# ParCar.net
KiCad netlist of a schematic drawn in Altium Designer
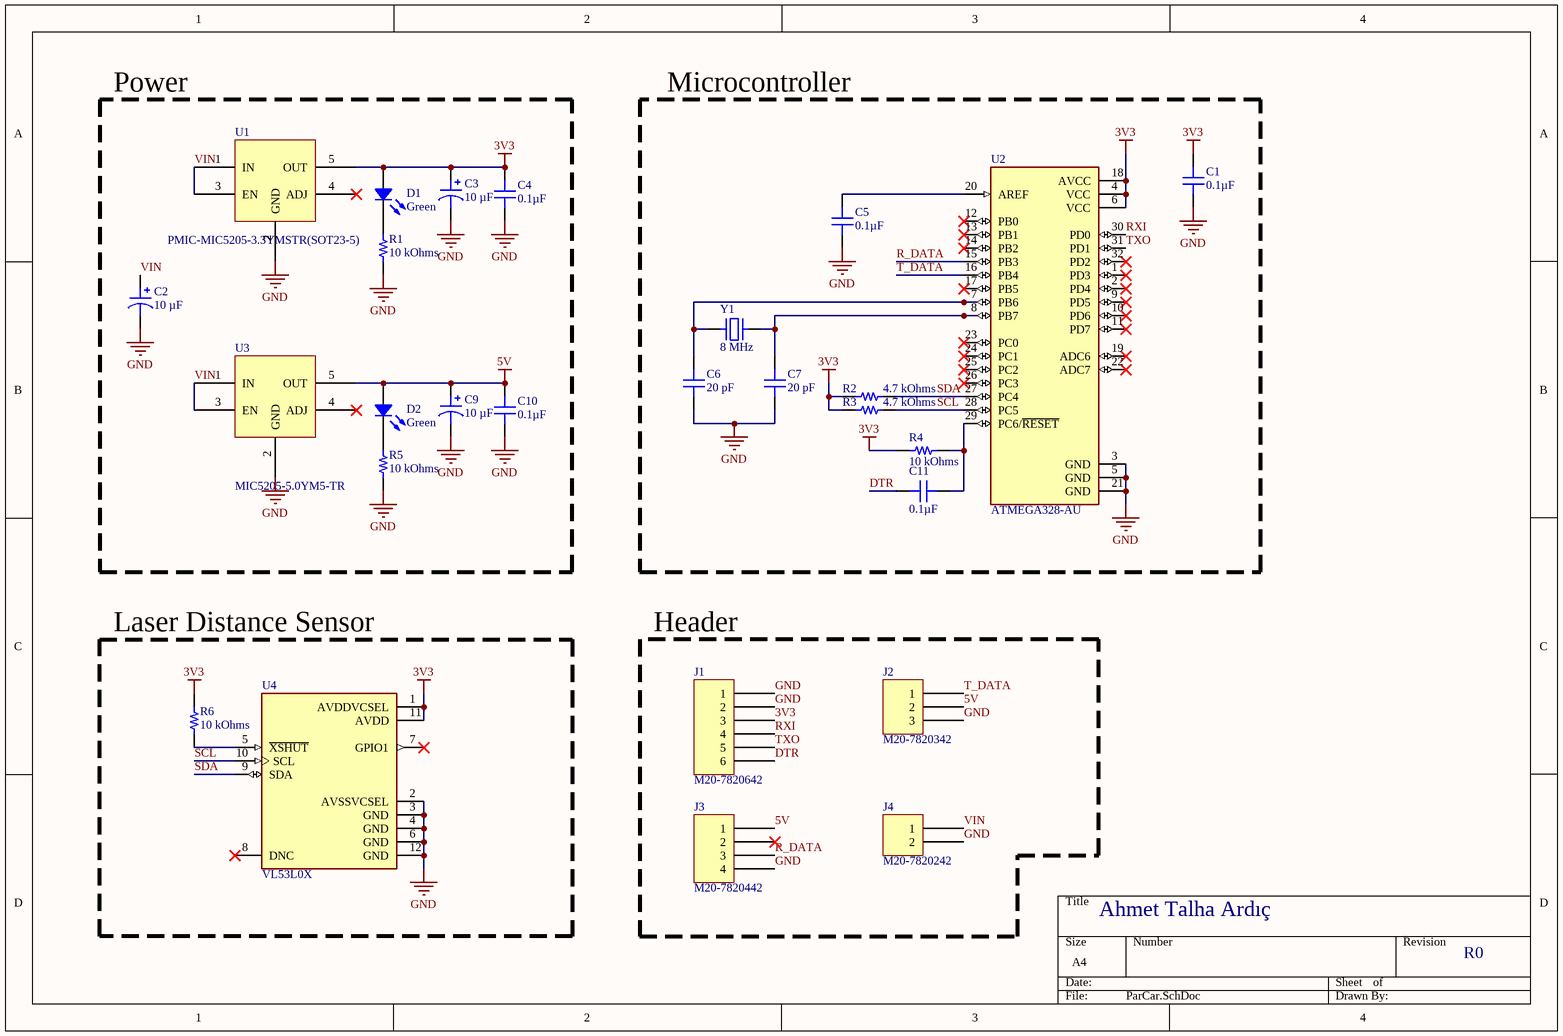
[diagram p0: ParCar.SchDoc]

(export (version "E")
  (design (tool "Eeschema 10.0.6"))
  (components
    (comp (ref "C1")
      (value "0.1µF")
      (footprint "CAP 0603_1608")
      (description "CAP CER 0.1UF 6.3V X7R 0603")
      (fields (field (name "PART NUMBER") "06036C104JAT2A") (field (name "MANUFACTURER") "AVX Corporation"))
      (libsource (lib "Celestial Altium Library - altium_library") (part "Capacitor"))
    )
    (comp (ref "C2")
      (value "10 µF")
      (footprint "CAP ALSMD 4.3MM H5.4MM")
      (description "CAP ALUM 10UF 20% 16V SMD")
      (fields (field (name "PART NUMBER") "UWX1C100MCL1GB") (field (name "MANUFACTURER") "Nichicon"))
      (libsource (lib "Celestial Altium Library - altium_library") (part "Polarised Capacitor"))
    )
    (comp (ref "C3")
      (value "10 µF")
      (footprint "CAP ALSMD 4.3MM H5.4MM")
      (description "CAP ALUM 10UF 20% 16V SMD")
      (fields (field (name "PART NUMBER") "UWX1C100MCL1GB") (field (name "MANUFACTURER") "Nichicon"))
      (libsource (lib "Celestial Altium Library - altium_library") (part "Polarised Capacitor"))
    )
    (comp (ref "C4")
      (value "0.1µF")
      (footprint "CAP 0603_1608")
      (description "CAP CER 0.1UF 6.3V X7R 0603")
      (fields (field (name "PART NUMBER") "06036C104JAT2A") (field (name "MANUFACTURER") "AVX Corporation"))
      (libsource (lib "Celestial Altium Library - altium_library") (part "Capacitor"))
    )
    (comp (ref "C5")
      (value "0.1µF")
      (footprint "CAP 0603_1608")
      (description "CAP CER 0.1UF 6.3V X7R 0603")
      (fields (field (name "PART NUMBER") "06036C104JAT2A") (field (name "MANUFACTURER") "AVX Corporation"))
      (libsource (lib "Celestial Altium Library - altium_library") (part "Capacitor"))
    )
    (comp (ref "C6")
      (value "20 pF")
      (footprint "CAP 0603_1608")
      (description "CAP CER 20PF 10V X8R 0603")
      (fields (field (name "PART NUMBER") "C0603C200G8HAC7867") (field (name "MANUFACTURER") "KEMET"))
      (libsource (lib "Celestial Altium Library - altium_library") (part "Capacitor"))
    )
    (comp (ref "C7")
      (value "20 pF")
      (footprint "CAP 0603_1608")
      (description "CAP CER 20PF 10V X8R 0603")
      (fields (field (name "PART NUMBER") "C0603C200G8HAC7867") (field (name "MANUFACTURER") "KEMET"))
      (libsource (lib "Celestial Altium Library - altium_library") (part "Capacitor"))
    )
    (comp (ref "C9")
      (value "10 µF")
      (footprint "CAP ALSMD 4.3MM H5.4MM")
      (description "CAP ALUM 10UF 20% 16V SMD")
      (fields (field (name "PART NUMBER") "UWX1C100MCL1GB") (field (name "MANUFACTURER") "Nichicon"))
      (libsource (lib "Celestial Altium Library - altium_library") (part "Polarised Capacitor"))
    )
    (comp (ref "C10")
      (value "0.1µF")
      (footprint "CAP 0603_1608")
      (description "CAP CER 0.1UF 6.3V X7R 0603")
      (fields (field (name "PART NUMBER") "06036C104JAT2A") (field (name "MANUFACTURER") "AVX Corporation"))
      (libsource (lib "Celestial Altium Library - altium_library") (part "Capacitor"))
    )
    (comp (ref "C11")
      (value "0.1µF")
      (footprint "CAP 0603_1608")
      (description "CAP CER 0.1UF 6.3V X7R 0603")
      (fields (field (name "PART NUMBER") "06036C104JAT2A") (field (name "MANUFACTURER") "AVX Corporation"))
      (libsource (lib "Celestial Altium Library - altium_library") (part "Capacitor"))
    )
    (comp (ref "D1")
      (value "Green")
      (footprint "LED 0805_2012 GREEN")
      (description "LED GREEN CLEAR SMD")
      (fields
        (field (name "PART NUMBER") "SML-LX0805GC-TR")
        (field (name "MANUFACTURER") "Lumex Opto/Components Inc.")
      )
      (libsource (lib "Celestial Altium Library - altium_library") (part "LED"))
    )
    (comp (ref "D2")
      (value "Green")
      (footprint "LED 0805_2012 GREEN")
      (description "LED GREEN CLEAR SMD")
      (fields
        (field (name "PART NUMBER") "SML-LX0805GC-TR")
        (field (name "MANUFACTURER") "Lumex Opto/Components Inc.")
      )
      (libsource (lib "Celestial Altium Library - altium_library") (part "LED"))
    )
    (comp (ref "J1")
      (value "M20-7820642")
      (footprint "HARWIN M20-7820645")
      (description "CONN RCPT 6POS 0.1 GOLD PCB")
      (fields (field (name "MANUFACTURER") "Harwin Inc."))
      (libsource (lib "Celestial Altium Library - altium_library") (part "6 Pin"))
    )
    (comp (ref "J2")
      (value "M20-7820342")
      (footprint "HARWIN M20-7820345")
      (description "CONN RCPT 3POS 0.1 GOLD PCB")
      (fields (field (name "MANUFACTURER") "Harwin Inc."))
      (libsource (lib "Celestial Altium Library - altium_library") (part "3 Pin"))
    )
    (comp (ref "J3")
      (value "M20-7820442")
      (footprint "HARWIN M20-7820445")
      (description "CONN RCPT 4POS 0.1 GOLD PCB")
      (fields (field (name "MANUFACTURER") "Harwin Inc."))
      (libsource (lib "Celestial Altium Library - altium_library") (part "4 Pin"))
    )
    (comp (ref "J4")
      (value "M20-7820242")
      (footprint "HARWIN M20-7820245")
      (description "CONN RCPT 2POS 0.1 GOLD PCB")
      (fields (field (name "MANUFACTURER") "Harwin Inc."))
      (libsource (lib "Celestial Altium Library - altium_library") (part "2 Pin"))
    )
    (comp (ref "R1")
      (value "10 kOhms")
      (footprint "RES 0603_1608")
      (description "RES SMD 10K OHM 5% 1/5W 0603")
      (fields
        (field (name "PART NUMBER") "ERJ-P03J103V")
        (field (name "MANUFACTURER") "Panasonic Electronic Components")
      )
      (libsource (lib "Celestial Altium Library - altium_library") (part "Resistor"))
    )
    (comp (ref "R2")
      (value "4.7 kOhms")
      (footprint "RES 0603_1608")
      (description "RES SMD 4.7K OHM 1% 1/10W 0603")
      (fields
        (field (name "PART NUMBER") "ERJ-3EKF4701V")
        (field (name "MANUFACTURER") "Panasonic Electronic Components")
      )
      (libsource (lib "Celestial Altium Library - altium_library") (part "Resistor"))
    )
    (comp (ref "R3")
      (value "4.7 kOhms")
      (footprint "RES 0603_1608")
      (description "RES SMD 4.7K OHM 1% 1/10W 0603")
      (fields
        (field (name "PART NUMBER") "ERJ-3EKF4701V")
        (field (name "MANUFACTURER") "Panasonic Electronic Components")
      )
      (libsource (lib "Celestial Altium Library - altium_library") (part "Resistor"))
    )
    (comp (ref "R4")
      (value "10 kOhms")
      (footprint "RES 0603_1608")
      (description "RES SMD 10K OHM 5% 1/4W 0603")
      (fields (field (name "PART NUMBER") "RCS060310K0JNEA") (field (name "MANUFACTURER") "Vishay Dale"))
      (libsource (lib "Celestial Altium Library - altium_library") (part "Resistor"))
    )
    (comp (ref "R5")
      (value "10 kOhms")
      (footprint "RES 0603_1608")
      (description "RES SMD 10K OHM 5% 1/5W 0603")
      (fields
        (field (name "PART NUMBER") "ERJ-P03J103V")
        (field (name "MANUFACTURER") "Panasonic Electronic Components")
      )
      (libsource (lib "Celestial Altium Library - altium_library") (part "Resistor"))
    )
    (comp (ref "R6")
      (value "10 kOhms")
      (footprint "RES 0603_1608")
      (description "RES SMD 10K OHM 5% 1/5W 0603")
      (fields
        (field (name "PART NUMBER") "ERJ-P03J103V")
        (field (name "MANUFACTURER") "Panasonic Electronic Components")
      )
      (libsource (lib "Celestial Altium Library - altium_library") (part "Resistor"))
    )
    (comp (ref "U1")
      (value "PMIC-MIC5205-3.3YMSTR(SOT23-5)")
      (footprint "PMIC-MIC5205-3.3YMSTR(SOT23-5)")
      (description "Linear Voltage Regulator IC 1 Output 150mA SOT-23-5")
      (libsource (lib "ParCar") (part "PMIC-MIC5205-3.3YMSTR(SOT23-5)"))
    )
    (comp (ref "U2")
      (value "ATMEGA328-AU")
      (footprint "ATMEGA328-AU")
      (description "AVR AVRÂ® ATmega Microcontroller IC 8-Bit 20MHz 32KB (16K x 16) FLASH 32-TQFP (7x7)")
      (libsource (lib "ParCar") (part "ATMEGA328-AU"))
    )
    (comp (ref "U3")
      (value "MIC5205-5.0YM5-TR")
      (footprint "PMIC-MIC5205-3.3YMSTR(SOT23-5)")
      (description "Linear Voltage Regulator IC Positive Fixed 1 Output 150mA SOT-23-5")
      (libsource (lib "ParCar") (part "MIC5205-5.0YM5-TR"))
    )
    (comp (ref "U4")
      (value "VL53L0X")
      (footprint "VL53L0X")
      (description "VL53L0X - Light, 3D Time-of-Flight _ToF_")
      (libsource (lib "ParCar") (part "VL53L0X"))
    )
    (comp (ref "Y1")
      (value "8 MHz")
      (footprint "ABRACON ABLS")
      (description "CRYSTAL 8.0000MHZ 18PF SMD")
      (fields (field (name "PART NUMBER") "ABLS-8.000MHZ-SD7Y-T") (field (name "MANUFACTURER") "Abracon LLC"))
      (libsource (lib "Celestial Altium Library - altium_library") (part "Abracon Crystal ABLS"))
    )
  )
  (nets
    (net (code "1") (name "/DTR") (class "Default")
      (node (ref "C11") (pin "1") (pinfunction "1_1") (pintype "passive"))
      (node (ref "J1") (pin "6") (pinfunction "6_6") (pintype "passive"))
    )
    (net (code "2") (name "/RXI") (class "Default")
      (node (ref "J1") (pin "4") (pinfunction "4_4") (pintype "passive"))
      (node (ref "U2") (pin "30") (pinfunction "PD0_30") (pintype "bidirectional"))
    )
    (net (code "3") (name "/R_DATA") (class "Default")
      (node (ref "J3") (pin "3") (pinfunction "3_3") (pintype "passive"))
      (node (ref "U2") (pin "15") (pinfunction "PB3_15") (pintype "bidirectional"))
    )
    (net (code "4") (name "/SCL") (class "Default")
      (node (ref "R3") (pin "1") (pinfunction "1_1") (pintype "passive"))
      (node (ref "U2") (pin "28") (pinfunction "PC5_28") (pintype "bidirectional"))
      (node (ref "U4") (pin "10") (pinfunction "SCL_10") (pintype "input"))
    )
    (net (code "5") (name "/SDA") (class "Default")
      (node (ref "R2") (pin "1") (pinfunction "1_1") (pintype "passive"))
      (node (ref "U2") (pin "27") (pinfunction "PC4_27") (pintype "bidirectional"))
      (node (ref "U4") (pin "9") (pinfunction "SDA_9") (pintype "bidirectional"))
    )
    (net (code "6") (name "/TXO") (class "Default")
      (node (ref "J1") (pin "5") (pinfunction "5_5") (pintype "passive"))
      (node (ref "U2") (pin "31") (pinfunction "PD1_31") (pintype "bidirectional"))
    )
    (net (code "7") (name "/T_DATA") (class "Default")
      (node (ref "J2") (pin "1") (pinfunction "1_1") (pintype "passive"))
      (node (ref "U2") (pin "16") (pinfunction "PB4_16") (pintype "bidirectional"))
    )
    (net (code "8") (name "/VIN") (class "Default")
      (node (ref "C2") (pin "1") (pinfunction "1_1") (pintype "passive"))
      (node (ref "J4") (pin "1") (pinfunction "1_1") (pintype "passive"))
      (node (ref "U1") (pin "1") (pinfunction "IN_1") (pintype "passive"))
      (node (ref "U1") (pin "3") (pinfunction "EN_3") (pintype "passive"))
      (node (ref "U3") (pin "1") (pinfunction "IN_1") (pintype "passive"))
      (node (ref "U3") (pin "3") (pinfunction "EN_3") (pintype "passive"))
    )
    (net (code "9") (name "3V3") (class "Default")
      (node (ref "C1") (pin "2") (pinfunction "2_2") (pintype "passive"))
      (node (ref "C3") (pin "1") (pinfunction "1_1") (pintype "passive"))
      (node (ref "C4") (pin "2") (pinfunction "2_2") (pintype "passive"))
      (node (ref "D1") (pin "1") (pinfunction "1_1") (pintype "passive"))
      (node (ref "J1") (pin "3") (pinfunction "3_3") (pintype "passive"))
      (node (ref "R2") (pin "2") (pinfunction "2_2") (pintype "passive"))
      (node (ref "R3") (pin "2") (pinfunction "2_2") (pintype "passive"))
      (node (ref "R4") (pin "1") (pinfunction "1_1") (pintype "passive"))
      (node (ref "R6") (pin "2") (pinfunction "2_2") (pintype "passive"))
      (node (ref "U1") (pin "5") (pinfunction "OUT_5") (pintype "passive"))
      (node (ref "U2") (pin "18") (pinfunction "AVCC_18") (pintype "power_in"))
      (node (ref "U2") (pin "4") (pinfunction "VCC_4") (pintype "power_in"))
      (node (ref "U2") (pin "6") (pinfunction "VCC_6") (pintype "power_in"))
      (node (ref "U4") (pin "1") (pinfunction "AVDDVCSEL_1") (pintype "power_in"))
      (node (ref "U4") (pin "11") (pinfunction "AVDD_11") (pintype "power_in"))
    )
    (net (code "10") (name "5V") (class "Default")
      (node (ref "C10") (pin "2") (pinfunction "2_2") (pintype "passive"))
      (node (ref "C9") (pin "1") (pinfunction "1_1") (pintype "passive"))
      (node (ref "D2") (pin "1") (pinfunction "1_1") (pintype "passive"))
      (node (ref "J2") (pin "2") (pinfunction "2_2") (pintype "passive"))
      (node (ref "J3") (pin "1") (pinfunction "1_1") (pintype "passive"))
      (node (ref "U3") (pin "5") (pinfunction "OUT_5") (pintype "passive"))
    )
    (net (code "11") (name "GND") (class "Default")
      (node (ref "C1") (pin "1") (pinfunction "1_1") (pintype "passive"))
      (node (ref "C10") (pin "1") (pinfunction "1_1") (pintype "passive"))
      (node (ref "C2") (pin "2") (pinfunction "2_2") (pintype "passive"))
      (node (ref "C3") (pin "2") (pinfunction "2_2") (pintype "passive"))
      (node (ref "C4") (pin "1") (pinfunction "1_1") (pintype "passive"))
      (node (ref "C5") (pin "1") (pinfunction "1_1") (pintype "passive"))
      (node (ref "C6") (pin "1") (pinfunction "1_1") (pintype "passive"))
      (node (ref "C7") (pin "1") (pinfunction "1_1") (pintype "passive"))
      (node (ref "C9") (pin "2") (pinfunction "2_2") (pintype "passive"))
      (node (ref "J1") (pin "1") (pinfunction "1_1") (pintype "passive"))
      (node (ref "J1") (pin "2") (pinfunction "2_2") (pintype "passive"))
      (node (ref "J2") (pin "3") (pinfunction "3_3") (pintype "passive"))
      (node (ref "J3") (pin "4") (pinfunction "4_4") (pintype "passive"))
      (node (ref "J4") (pin "2") (pinfunction "2_2") (pintype "passive"))
      (node (ref "R1") (pin "1") (pinfunction "1_1") (pintype "passive"))
      (node (ref "R5") (pin "1") (pinfunction "1_1") (pintype "passive"))
      (node (ref "U1") (pin "2") (pinfunction "GND_2") (pintype "passive"))
      (node (ref "U2") (pin "21") (pinfunction "GND_21") (pintype "power_in"))
      (node (ref "U2") (pin "3") (pinfunction "GND_3") (pintype "power_in"))
      (node (ref "U2") (pin "5") (pinfunction "GND_5") (pintype "power_in"))
      (node (ref "U3") (pin "2") (pinfunction "GND_2") (pintype "passive"))
      (node (ref "U4") (pin "12") (pinfunction "GND_12") (pintype "power_in"))
      (node (ref "U4") (pin "2") (pinfunction "AVSSVCSEL_2") (pintype "power_in"))
      (node (ref "U4") (pin "3") (pinfunction "GND_3") (pintype "power_in"))
      (node (ref "U4") (pin "4") (pinfunction "GND_4") (pintype "power_in"))
      (node (ref "U4") (pin "6") (pinfunction "GND_6") (pintype "power_in"))
    )
    (net (code "12") (name "Net-(D1-Pad2)") (class "Default")
      (node (ref "D1") (pin "2") (pinfunction "2_2") (pintype "passive"))
      (node (ref "R1") (pin "2") (pinfunction "2_2") (pintype "passive"))
    )
    (net (code "13") (name "Net-(D2-Pad2)") (class "Default")
      (node (ref "D2") (pin "2") (pinfunction "2_2") (pintype "passive"))
      (node (ref "R5") (pin "2") (pinfunction "2_2") (pintype "passive"))
    )
    (net (code "14") (name "Net-(U2-AREF)") (class "Default")
      (node (ref "C5") (pin "2") (pinfunction "2_2") (pintype "passive"))
      (node (ref "U2") (pin "20") (pinfunction "AREF_20") (pintype "input"))
    )
    (net (code "15") (name "Net-(U2-PB6)") (class "Default")
      (node (ref "C6") (pin "2") (pinfunction "2_2") (pintype "passive"))
      (node (ref "U2") (pin "7") (pinfunction "PB6_7") (pintype "bidirectional"))
      (node (ref "Y1") (pin "2") (pinfunction "2_2") (pintype "passive"))
    )
    (net (code "16") (name "Net-(U2-PB7)") (class "Default")
      (node (ref "C7") (pin "2") (pinfunction "2_2") (pintype "passive"))
      (node (ref "U2") (pin "8") (pinfunction "PB7_8") (pintype "bidirectional"))
      (node (ref "Y1") (pin "1") (pinfunction "1_1") (pintype "passive"))
    )
    (net (code "17") (name "Net-(U2-PC6{slash}~{RESET})") (class "Default")
      (node (ref "C11") (pin "2") (pinfunction "2_2") (pintype "passive"))
      (node (ref "R4") (pin "2") (pinfunction "2_2") (pintype "passive"))
      (node (ref "U2") (pin "29") (pinfunction "PC6/~{RESET}_29") (pintype "bidirectional"))
    )
    (net (code "18") (name "Net-(U4-~{XSHUT})") (class "Default")
      (node (ref "R6") (pin "1") (pinfunction "1_1") (pintype "passive"))
      (node (ref "U4") (pin "5") (pinfunction "~{XSHUT}_5") (pintype "input"))
    )
    (net (code "19") (name "unconnected-(J3-Pad2)") (class "Default")
      (node (ref "J3") (pin "2") (pinfunction "2_2") (pintype "passive+no_connect"))
    )
    (net (code "20") (name "unconnected-(U1-ADJ-Pad4)") (class "Default")
      (node (ref "U1") (pin "4") (pinfunction "ADJ_4") (pintype "passive+no_connect"))
    )
    (net (code "21") (name "unconnected-(U2-ADC6-Pad19)") (class "Default")
      (node (ref "U2") (pin "19") (pinfunction "ADC6_19") (pintype "bidirectional+no_connect"))
    )
    (net (code "22") (name "unconnected-(U2-ADC7-Pad22)") (class "Default")
      (node (ref "U2") (pin "22") (pinfunction "ADC7_22") (pintype "bidirectional+no_connect"))
    )
    (net (code "23") (name "unconnected-(U2-PB0-Pad12)") (class "Default")
      (node (ref "U2") (pin "12") (pinfunction "PB0_12") (pintype "bidirectional+no_connect"))
    )
    (net (code "24") (name "unconnected-(U2-PB1-Pad13)") (class "Default")
      (node (ref "U2") (pin "13") (pinfunction "PB1_13") (pintype "bidirectional+no_connect"))
    )
    (net (code "25") (name "unconnected-(U2-PB2-Pad14)") (class "Default")
      (node (ref "U2") (pin "14") (pinfunction "PB2_14") (pintype "bidirectional+no_connect"))
    )
    (net (code "26") (name "unconnected-(U2-PB5-Pad17)") (class "Default")
      (node (ref "U2") (pin "17") (pinfunction "PB5_17") (pintype "bidirectional+no_connect"))
    )
    (net (code "27") (name "unconnected-(U2-PC0-Pad23)") (class "Default")
      (node (ref "U2") (pin "23") (pinfunction "PC0_23") (pintype "bidirectional+no_connect"))
    )
    (net (code "28") (name "unconnected-(U2-PC1-Pad24)") (class "Default")
      (node (ref "U2") (pin "24") (pinfunction "PC1_24") (pintype "bidirectional+no_connect"))
    )
    (net (code "29") (name "unconnected-(U2-PC2-Pad25)") (class "Default")
      (node (ref "U2") (pin "25") (pinfunction "PC2_25") (pintype "bidirectional+no_connect"))
    )
    (net (code "30") (name "unconnected-(U2-PC3-Pad26)") (class "Default")
      (node (ref "U2") (pin "26") (pinfunction "PC3_26") (pintype "bidirectional+no_connect"))
    )
    (net (code "31") (name "unconnected-(U2-PD2-Pad32)") (class "Default")
      (node (ref "U2") (pin "32") (pinfunction "PD2_32") (pintype "bidirectional+no_connect"))
    )
    (net (code "32") (name "unconnected-(U2-PD3-Pad1)") (class "Default")
      (node (ref "U2") (pin "1") (pinfunction "PD3_1") (pintype "bidirectional+no_connect"))
    )
    (net (code "33") (name "unconnected-(U2-PD4-Pad2)") (class "Default")
      (node (ref "U2") (pin "2") (pinfunction "PD4_2") (pintype "bidirectional+no_connect"))
    )
    (net (code "34") (name "unconnected-(U2-PD5-Pad9)") (class "Default")
      (node (ref "U2") (pin "9") (pinfunction "PD5_9") (pintype "bidirectional+no_connect"))
    )
    (net (code "35") (name "unconnected-(U2-PD6-Pad10)") (class "Default")
      (node (ref "U2") (pin "10") (pinfunction "PD6_10") (pintype "bidirectional+no_connect"))
    )
    (net (code "36") (name "unconnected-(U2-PD7-Pad11)") (class "Default")
      (node (ref "U2") (pin "11") (pinfunction "PD7_11") (pintype "bidirectional+no_connect"))
    )
    (net (code "37") (name "unconnected-(U3-ADJ-Pad4)") (class "Default")
      (node (ref "U3") (pin "4") (pinfunction "ADJ_4") (pintype "passive+no_connect"))
    )
    (net (code "38") (name "unconnected-(U4-DNC-Pad8)") (class "Default")
      (node (ref "U4") (pin "8") (pinfunction "DNC_8") (pintype "power_in+no_connect"))
    )
    (net (code "39") (name "unconnected-(U4-GPIO1-Pad7)") (class "Default")
      (node (ref "U4") (pin "7") (pinfunction "GPIO1_7") (pintype "output+no_connect"))
    )
  )
)
